# Sensor_post.net
KiCad netlist of a schematic drawn in EAGLE
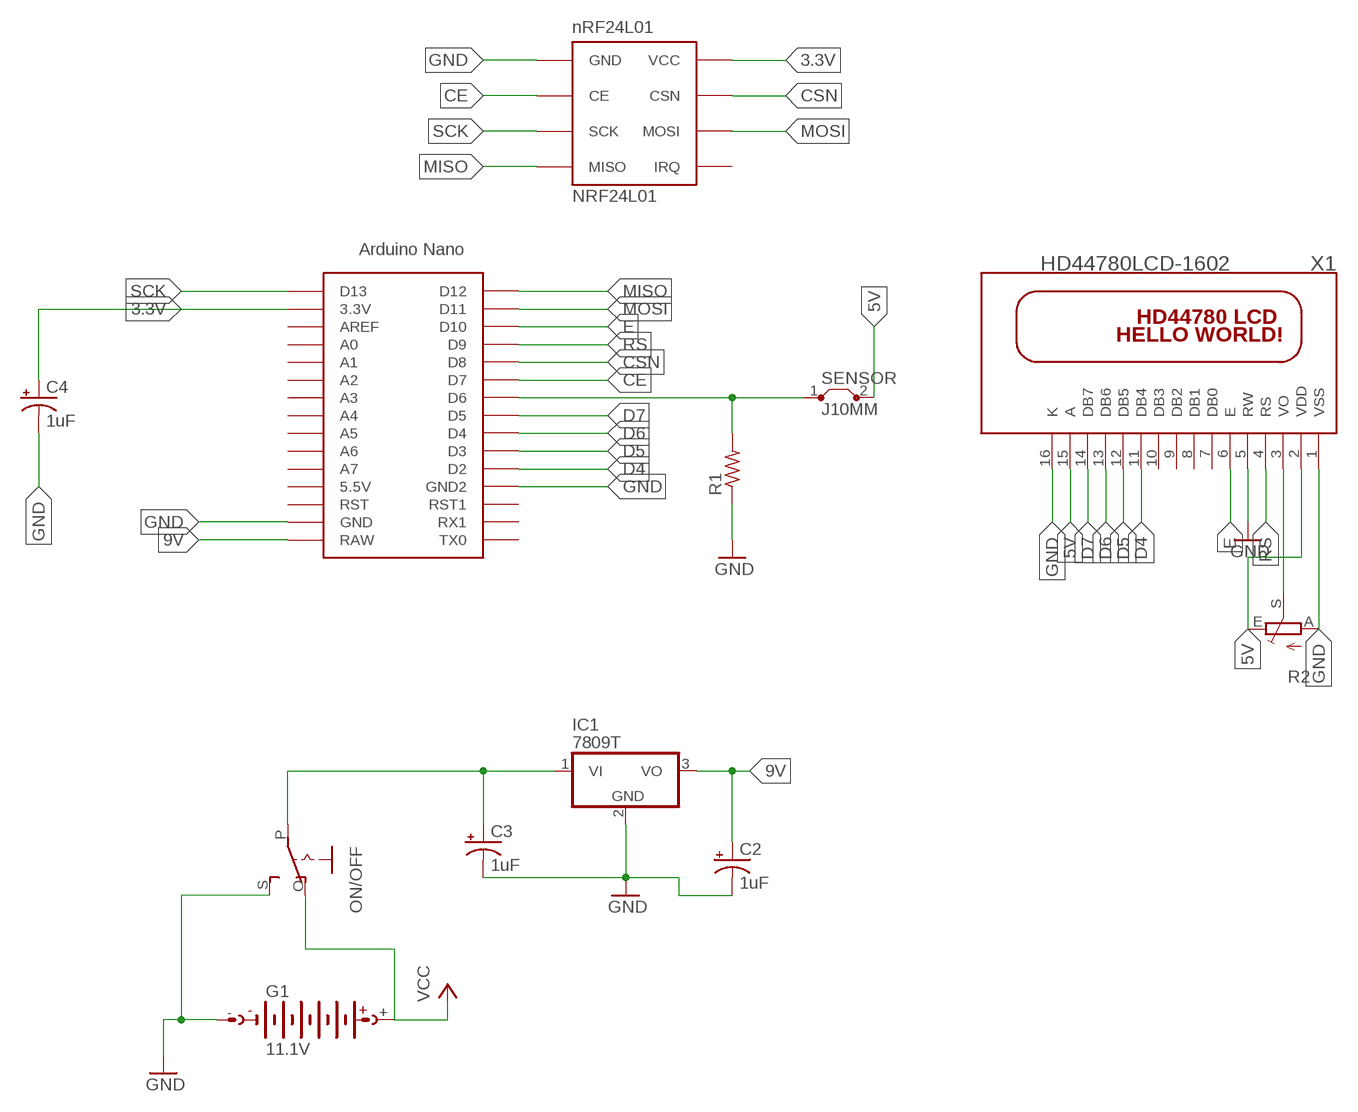
[diagram p0: schematic, sheet 1]

(export (version "E")
  (design (tool "Eeschema 10.0.6"))
  (components
    (comp (ref "C2")
      (value "1uF")
      (footprint "eagle-import:E2,5-7")
      (libsource (lib "eagle-import") (part "CPOL-USE2.5-7"))
    )
    (comp (ref "C3")
      (value "1uF")
      (footprint "eagle-import:E2,5-7")
      (libsource (lib "eagle-import") (part "CPOL-USE2.5-7"))
    )
    (comp (ref "C4")
      (value "1uF")
      (footprint "eagle-import:E2,5-7")
      (libsource (lib "eagle-import") (part "CPOL-USE2.5-7"))
    )
    (comp (ref "G1")
      (value "11.1V")
      (footprint "eagle-import:AB9V")
      (libsource (lib "eagle-import") (part "AB9V"))
    )
    (comp (ref "IC1")
      (value "7809T")
      (footprint "eagle-import:TO220V")
      (libsource (lib "eagle-import") (part "78TV05"))
    )
    (comp (ref "NRF24L1")
      (value "NRF24L01")
      (footprint "eagle-import:NRF24L01")
      (libsource (lib "eagle-import") (part "NRF24L01"))
    )
    (comp (ref "ON/OFF")
      (value "EG1218S")
      (footprint "eagle-import:EG1218")
      (libsource (lib "eagle-import") (part "EG1218S"))
    )
    (comp (ref "R1")
      (value "R-US_0207/10")
      (footprint "eagle-import:0207_10")
      (libsource (lib "eagle-import") (part "R-US_0207/10"))
    )
    (comp (ref "R2")
      (value "TRIM_EU-CA9V")
      (footprint "eagle-import:CA9V")
      (libsource (lib "eagle-import") (part "TRIM_EU-CA9V"))
    )
    (comp (ref "SENSOR")
      (value "J10MM")
      (footprint "eagle-import:10")
      (libsource (lib "eagle-import") (part "J10MM"))
    )
    (comp (ref "U$1")
      (value "NANO")
      (footprint "eagle-import:NANO")
      (libsource (lib "eagle-import") (part "NANO"))
    )
    (comp (ref "X1")
      (value "HD44780LCD-1602")
      (footprint "eagle-import:LCD1602")
      (libsource (lib "eagle-import") (part "HD44780LCD-1602"))
    )
  )
  (nets
    (net (code "1") (name "3.3V") (class "Default")
      (node (ref "C4") (pin "+") (pinfunction "+_+") (pintype "passive"))
      (node (ref "NRF24L1") (pin "VCC") (pinfunction "VCC_VCC") (pintype "bidirectional"))
      (node (ref "U$1") (pin "3.3V") (pinfunction "3.3V_3.3V") (pintype "bidirectional"))
    )
    (net (code "2") (name "5V") (class "Default")
      (node (ref "R2") (pin "E") (pinfunction "E_E") (pintype "passive"))
      (node (ref "SENSOR") (pin "2") (pinfunction "2_2") (pintype "passive"))
      (node (ref "X1") (pin "15") (pinfunction "A_15") (pintype "input"))
      (node (ref "X1") (pin "2") (pinfunction "VDD_2") (pintype "power_in"))
    )
    (net (code "3") (name "9V") (class "Default")
      (node (ref "C2") (pin "+") (pinfunction "+_+") (pintype "passive"))
      (node (ref "IC1") (pin "3") (pinfunction "VO_3") (pintype "passive"))
      (node (ref "U$1") (pin "RAW") (pinfunction "RAW_RAW") (pintype "bidirectional"))
    )
    (net (code "4") (name "CE") (class "Default")
      (node (ref "NRF24L1") (pin "CE") (pinfunction "CE_CE") (pintype "bidirectional"))
      (node (ref "U$1") (pin "D7") (pinfunction "D7_D7") (pintype "bidirectional"))
    )
    (net (code "5") (name "CSN") (class "Default")
      (node (ref "NRF24L1") (pin "CSN") (pinfunction "CSN_CSN") (pintype "bidirectional"))
      (node (ref "U$1") (pin "D8") (pinfunction "D8_D8") (pintype "bidirectional"))
    )
    (net (code "6") (name "D4") (class "Default")
      (node (ref "U$1") (pin "D2") (pinfunction "D2_D2") (pintype "bidirectional"))
      (node (ref "X1") (pin "11") (pinfunction "DB4_11") (pintype "bidirectional"))
    )
    (net (code "7") (name "D5") (class "Default")
      (node (ref "U$1") (pin "D3") (pinfunction "D3_D3") (pintype "bidirectional"))
      (node (ref "X1") (pin "12") (pinfunction "DB5_12") (pintype "bidirectional"))
    )
    (net (code "8") (name "D6") (class "Default")
      (node (ref "U$1") (pin "D4") (pinfunction "D4_D4") (pintype "bidirectional"))
      (node (ref "X1") (pin "13") (pinfunction "DB6_13") (pintype "bidirectional"))
    )
    (net (code "9") (name "D7") (class "Default")
      (node (ref "U$1") (pin "D5") (pinfunction "D5_D5") (pintype "bidirectional"))
      (node (ref "X1") (pin "14") (pinfunction "DB7_14") (pintype "bidirectional"))
    )
    (net (code "10") (name "E") (class "Default")
      (node (ref "U$1") (pin "D10") (pinfunction "D10_D10") (pintype "bidirectional"))
      (node (ref "X1") (pin "6") (pinfunction "E_6") (pintype "input"))
    )
    (net (code "11") (name "GND") (class "Default")
      (node (ref "C2") (pin "-") (pinfunction "-_-") (pintype "passive"))
      (node (ref "C3") (pin "-") (pinfunction "-_-") (pintype "passive"))
      (node (ref "C4") (pin "-") (pinfunction "-_-") (pintype "passive"))
      (node (ref "G1") (pin "-") (pinfunction "-_-") (pintype "passive"))
      (node (ref "IC1") (pin "2") (pinfunction "GND_2") (pintype "passive"))
      (node (ref "NRF24L1") (pin "GND") (pinfunction "GND_GND") (pintype "bidirectional"))
      (node (ref "ON/OFF") (pin "S") (pinfunction "S_S") (pintype "passive"))
      (node (ref "R1") (pin "1") (pinfunction "1_1") (pintype "passive"))
      (node (ref "R2") (pin "A") (pinfunction "A_A") (pintype "passive"))
      (node (ref "U$1") (pin "GND") (pinfunction "GND_GND") (pintype "bidirectional"))
      (node (ref "U$1") (pin "GND1") (pinfunction "GND2_GND1") (pintype "bidirectional"))
      (node (ref "X1") (pin "1") (pinfunction "VSS_1") (pintype "power_in"))
      (node (ref "X1") (pin "16") (pinfunction "K_16") (pintype "input"))
      (node (ref "X1") (pin "5") (pinfunction "RW_5") (pintype "input"))
    )
    (net (code "12") (name "MISO") (class "Default")
      (node (ref "NRF24L1") (pin "MISO") (pinfunction "MISO_MISO") (pintype "bidirectional"))
      (node (ref "U$1") (pin "D12") (pinfunction "D12_D12") (pintype "bidirectional"))
    )
    (net (code "13") (name "MOSI") (class "Default")
      (node (ref "NRF24L1") (pin "MOSI") (pinfunction "MOSI_MOSI") (pintype "bidirectional"))
      (node (ref "U$1") (pin "D11") (pinfunction "D11_D11") (pintype "bidirectional"))
    )
    (net (code "14") (name "Net-(IC1-VI)") (class "Default")
      (node (ref "C3") (pin "+") (pinfunction "+_+") (pintype "passive"))
      (node (ref "IC1") (pin "1") (pinfunction "VI_1") (pintype "input"))
      (node (ref "ON/OFF") (pin "P") (pinfunction "P_P") (pintype "passive"))
    )
    (net (code "15") (name "Net-(R1-Pad2)") (class "Default")
      (node (ref "R1") (pin "2") (pinfunction "2_2") (pintype "passive"))
      (node (ref "SENSOR") (pin "1") (pinfunction "1_1") (pintype "passive"))
      (node (ref "U$1") (pin "D6") (pinfunction "D6_D6") (pintype "bidirectional"))
    )
    (net (code "16") (name "Net-(X1-VO)") (class "Default")
      (node (ref "R2") (pin "S") (pinfunction "S_S") (pintype "passive"))
      (node (ref "X1") (pin "3") (pinfunction "VO_3") (pintype "input"))
    )
    (net (code "17") (name "RS") (class "Default")
      (node (ref "U$1") (pin "D9") (pinfunction "D9_D9") (pintype "bidirectional"))
      (node (ref "X1") (pin "4") (pinfunction "RS_4") (pintype "input"))
    )
    (net (code "18") (name "SCK") (class "Default")
      (node (ref "NRF24L1") (pin "SCK") (pinfunction "SCK_SCK") (pintype "bidirectional"))
      (node (ref "U$1") (pin "D13") (pinfunction "D13_D13") (pintype "bidirectional"))
    )
    (net (code "19") (name "VCC") (class "Default")
      (node (ref "G1") (pin "+") (pinfunction "+_+") (pintype "passive"))
      (node (ref "ON/OFF") (pin "O") (pinfunction "O_O") (pintype "passive"))
    )
    (net (code "20") (name "unconnected-(NRF24L1-PadIRQ)") (class "Default")
      (node (ref "NRF24L1") (pin "IRQ") (pinfunction "IRQ_IRQ") (pintype "bidirectional"))
    )
    (net (code "21") (name "unconnected-(U$1-5.5V-Pad5V)") (class "Default")
      (node (ref "U$1") (pin "5V") (pinfunction "5.5V_5V") (pintype "bidirectional"))
    )
    (net (code "22") (name "unconnected-(U$1-PadA0)") (class "Default")
      (node (ref "U$1") (pin "A0") (pinfunction "A0_A0") (pintype "bidirectional"))
    )
    (net (code "23") (name "unconnected-(U$1-PadA1)") (class "Default")
      (node (ref "U$1") (pin "A1") (pinfunction "A1_A1") (pintype "bidirectional"))
    )
    (net (code "24") (name "unconnected-(U$1-PadA2)") (class "Default")
      (node (ref "U$1") (pin "A2") (pinfunction "A2_A2") (pintype "bidirectional"))
    )
    (net (code "25") (name "unconnected-(U$1-PadA3)") (class "Default")
      (node (ref "U$1") (pin "A3") (pinfunction "A3_A3") (pintype "bidirectional"))
    )
    (net (code "26") (name "unconnected-(U$1-PadA4)") (class "Default")
      (node (ref "U$1") (pin "A4") (pinfunction "A4_A4") (pintype "bidirectional"))
    )
    (net (code "27") (name "unconnected-(U$1-PadA5)") (class "Default")
      (node (ref "U$1") (pin "A5") (pinfunction "A5_A5") (pintype "bidirectional"))
    )
    (net (code "28") (name "unconnected-(U$1-PadA6)") (class "Default")
      (node (ref "U$1") (pin "A6") (pinfunction "A6_A6") (pintype "bidirectional"))
    )
    (net (code "29") (name "unconnected-(U$1-PadA7)") (class "Default")
      (node (ref "U$1") (pin "A7") (pinfunction "A7_A7") (pintype "bidirectional"))
    )
    (net (code "30") (name "unconnected-(U$1-PadAREF)") (class "Default")
      (node (ref "U$1") (pin "AREF") (pinfunction "AREF_AREF") (pintype "bidirectional"))
    )
    (net (code "31") (name "unconnected-(U$1-PadRST)") (class "Default")
      (node (ref "U$1") (pin "RST") (pinfunction "RST_RST") (pintype "bidirectional"))
    )
    (net (code "32") (name "unconnected-(U$1-PadRST1)") (class "Default")
      (node (ref "U$1") (pin "RST1") (pinfunction "RST1_RST1") (pintype "bidirectional"))
    )
    (net (code "33") (name "unconnected-(U$1-PadRX1)") (class "Default")
      (node (ref "U$1") (pin "RX1") (pinfunction "RX1_RX1") (pintype "bidirectional"))
    )
    (net (code "34") (name "unconnected-(U$1-PadTX0)") (class "Default")
      (node (ref "U$1") (pin "TX0") (pinfunction "TX0_TX0") (pintype "bidirectional"))
    )
    (net (code "35") (name "unconnected-(X1-DB0-Pad7)") (class "Default")
      (node (ref "X1") (pin "7") (pinfunction "DB0_7") (pintype "bidirectional"))
    )
    (net (code "36") (name "unconnected-(X1-DB1-Pad8)") (class "Default")
      (node (ref "X1") (pin "8") (pinfunction "DB1_8") (pintype "bidirectional"))
    )
    (net (code "37") (name "unconnected-(X1-DB2-Pad9)") (class "Default")
      (node (ref "X1") (pin "9") (pinfunction "DB2_9") (pintype "bidirectional"))
    )
    (net (code "38") (name "unconnected-(X1-DB3-Pad10)") (class "Default")
      (node (ref "X1") (pin "10") (pinfunction "DB3_10") (pintype "bidirectional"))
    )
  )
)
